# Servo_tester_Shematic.net
KiCad netlist of a schematic drawn in EasyEDA Pro
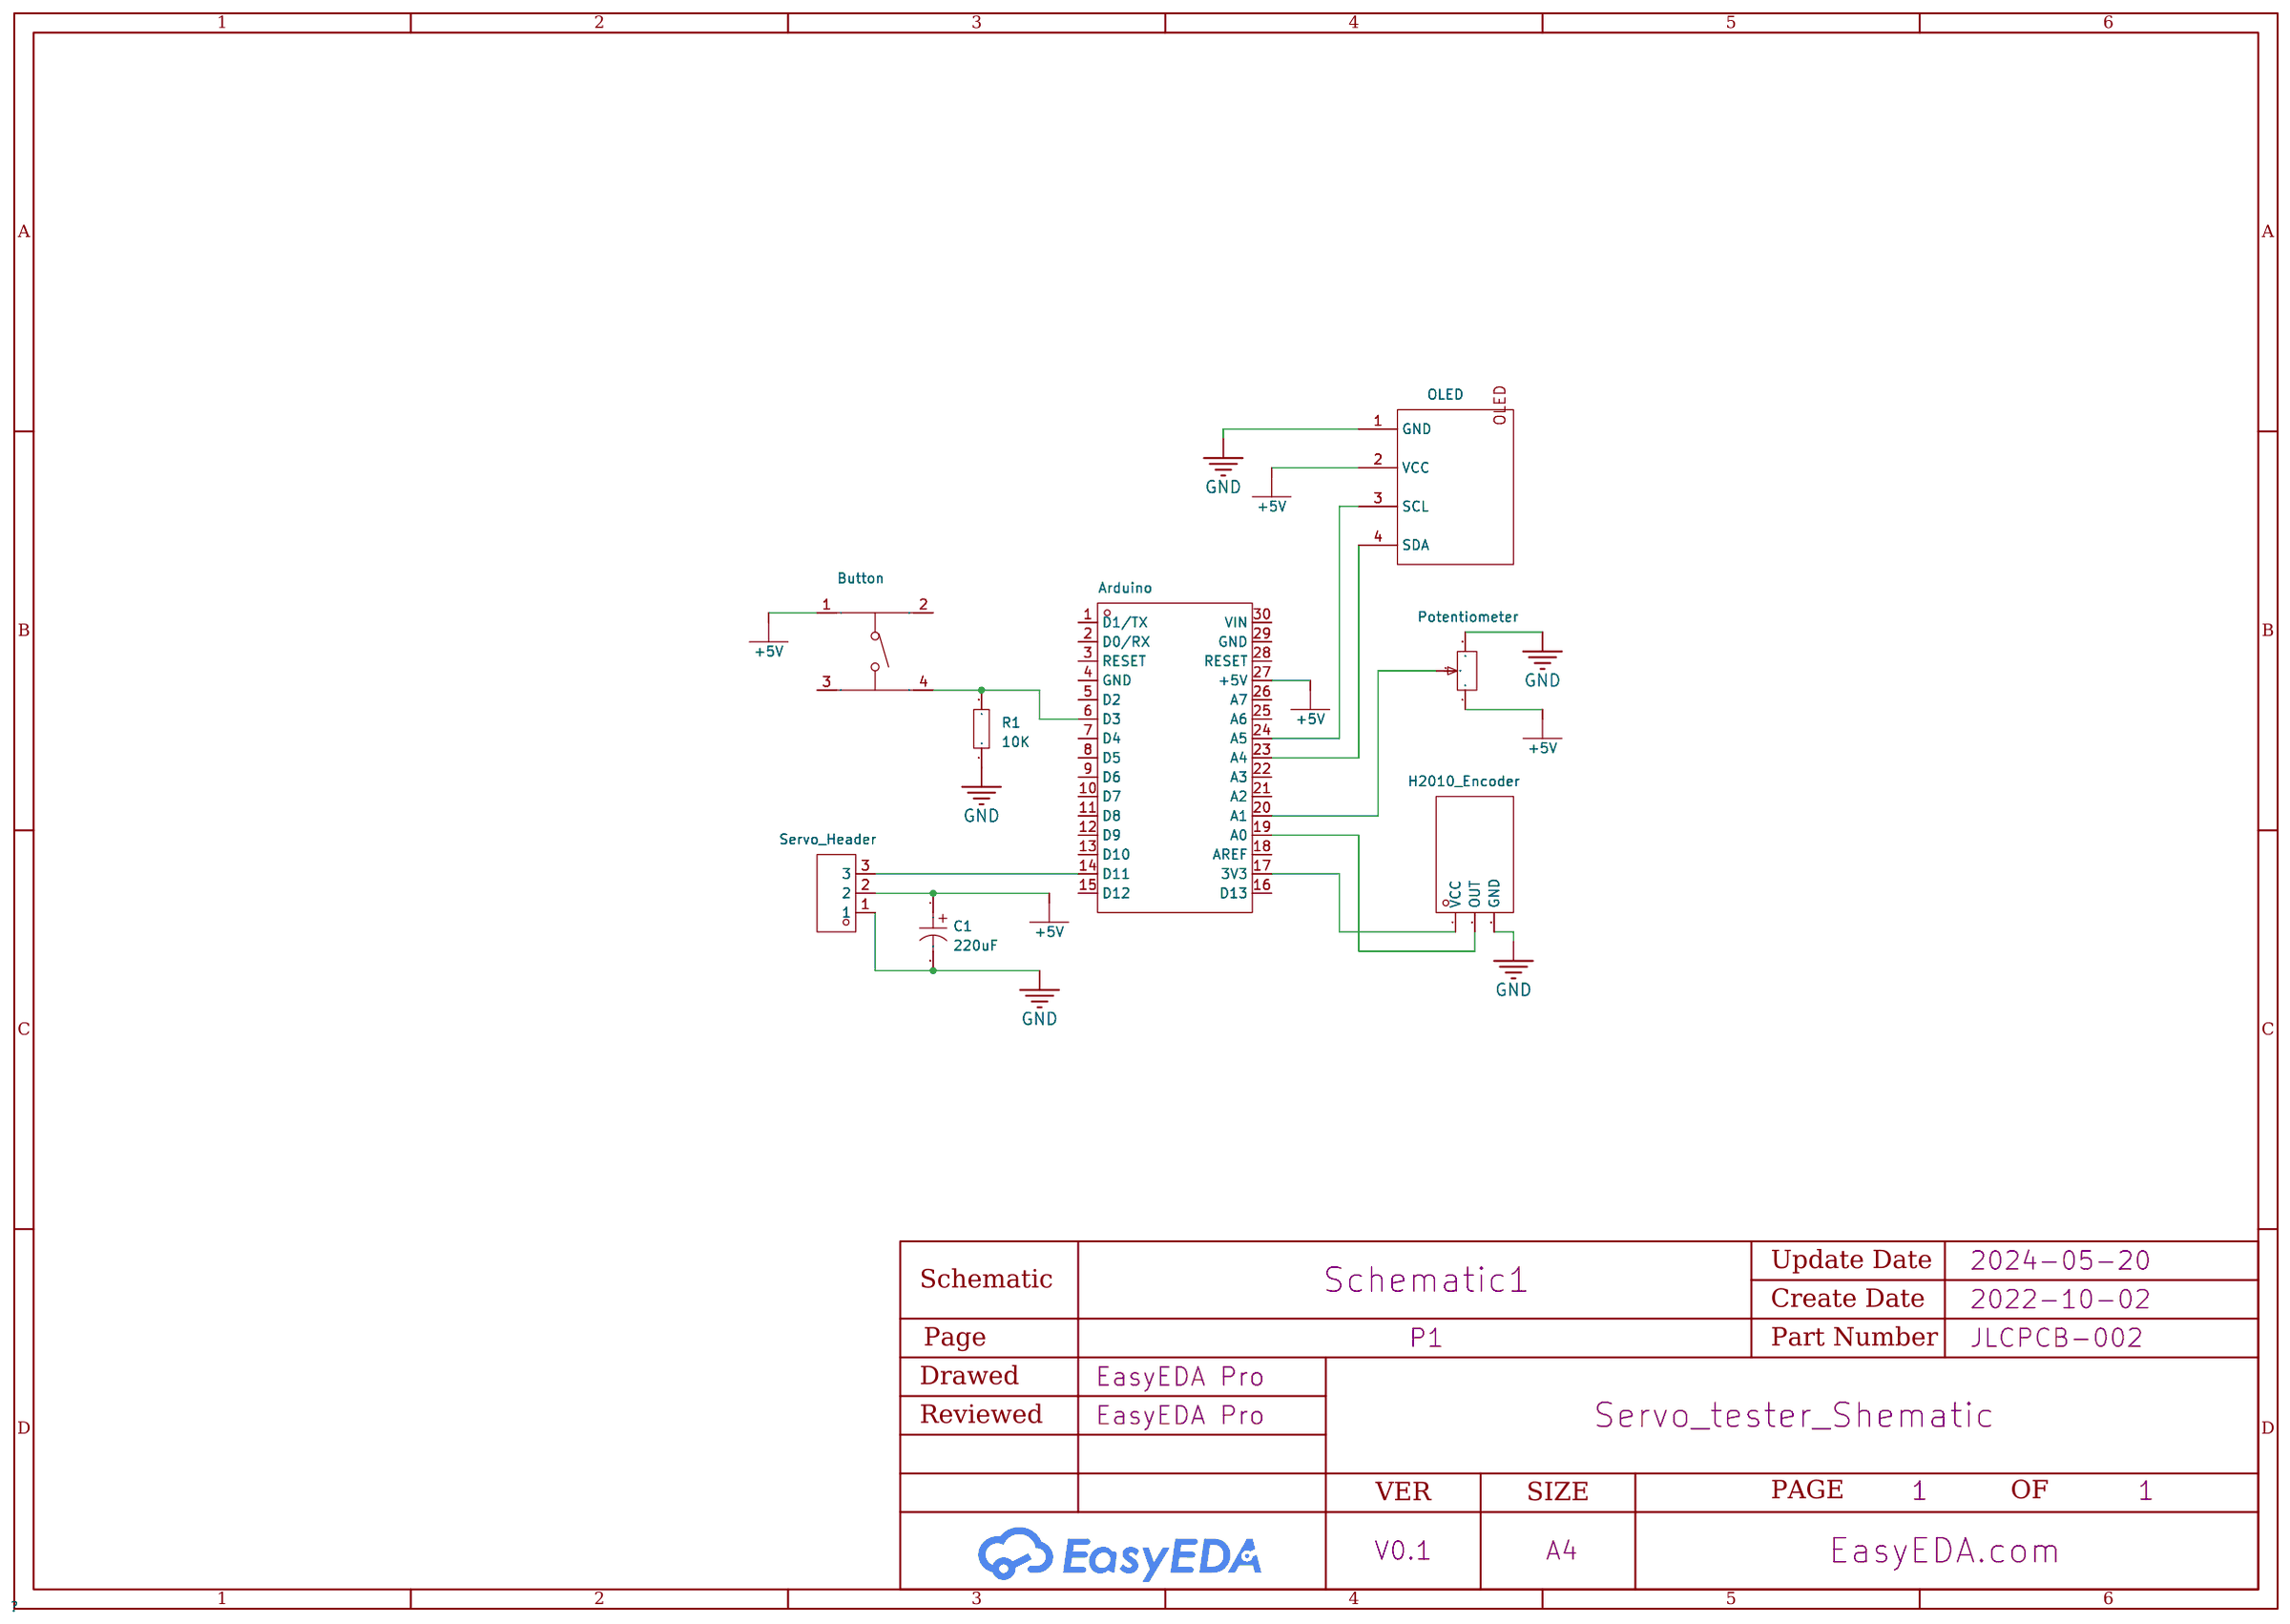
[diagram p0: schematic sheet]

(export (version "E")
  (design (tool "Eeschema 10.0.6"))
  (components
    (comp (ref "Arduino")
      (value "~")
      (footprint "easyedapro:COMM-TH_ARDUINO_NANO")
      (fields (field (name "Manufacturer Part") "ARDUINO_NANO"))
      (libsource (lib "easyedapro") (part "ARDUINO_NANO"))
    )
    (comp (ref "C1")
      (value "220uF")
      (footprint "easyedapro:CAP-TH_BD8.0-P3.50-D0.6-FD-2")
      (fields
        (field (name "Manufacturer Part") "KNH2220UF35V149EC0049")
        (field (name "Manufacturer") "KNSCHA(科尼盛)")
      )
      (libsource (lib "easyedapro") (part "KNH2220UF35V149EC0049"))
    )
    (comp (ref "H1")
      (value "Servo_Header")
      (footprint "easyedapro:HDR-TH_3P-P2.54-V-M")
      (fields
        (field (name "Manufacturer Part") "KH-2.54PH180-1X3P-L11.5")
        (field (name "Manufacturer") "kinghelm(金航标)")
      )
      (libsource (lib "easyedapro") (part "KH-2.54PH180-1X3P-L11.5"))
    )
    (comp (ref "H2010_Encoder")
      (value "POWER3-1")
      (footprint "easyedapro:CONN-TH_XH2.54-3P")
      (libsource (lib "easyedapro") (part "POWER3-1"))
    )
    (comp (ref "KEY1")
      (value "Button")
      (footprint "easyedapro:KEY-SMD_4P-L6.0-W6.0-P4.50-LS9.0")
      (libsource (lib "easyedapro") (part "BUTTON1"))
    )
    (comp (ref "OLED1")
      (value "OLED")
      (footprint "easyedapro:0.96OLED_4P")
      (fields (field (name "Manufacturer Part") "0.96OLED_4P_MODULE_JX"))
      (libsource (lib "easyedapro") (part "0.96OLED_4P_MODULE_JX"))
    )
    (comp (ref "R1")
      (value "10K")
      (footprint "easyedapro:RES-TH_BD2.5-L7.0-P11.00-D0.6-A")
      (libsource (lib "easyedapro") (part "10K_C9900023230"))
    )
    (comp (ref "U2")
      (value "Potentiometer")
      (footprint "easyedapro:RES-ADJ-SMD_VG039NCH")
      (fields (field (name "Manufacturer Part") "3*3Potentiometer-10kΩ20%"))
      (libsource (lib "easyedapro") (part "3*3POTENTIOMETER-10KΩ20%"))
    )
  )
  (nets
    (net (code "1") (name "+5V") (class "Default")
      (node (ref "Arduino") (pin "27") (pinfunction "+5V_27") (pintype "input"))
      (node (ref "C1") (pin "1") (pinfunction "1_1") (pintype "input"))
      (node (ref "H1") (pin "2") (pinfunction "2_2") (pintype "input"))
      (node (ref "KEY1") (pin "1") (pinfunction "1_1") (pintype "input"))
      (node (ref "OLED1") (pin "2") (pinfunction "VCC_2") (pintype "input"))
      (node (ref "U2") (pin "1") (pinfunction "1_1") (pintype "input"))
    )
    (net (code "2") (name "GND") (class "Default")
      (node (ref "C1") (pin "2") (pinfunction "2_2") (pintype "input"))
      (node (ref "H1") (pin "1") (pinfunction "1_1") (pintype "input"))
      (node (ref "H2010_Encoder") (pin "3") (pinfunction "GND_3") (pintype "unspecified"))
      (node (ref "OLED1") (pin "1") (pinfunction "GND_1") (pintype "input"))
      (node (ref "R1") (pin "1") (pinfunction "1_1") (pintype "input"))
      (node (ref "U2") (pin "3") (pinfunction "3_3") (pintype "input"))
    )
    (net (code "3") (name "Net-(Arduino-3V3)") (class "Default")
      (node (ref "Arduino") (pin "17") (pinfunction "3V3_17") (pintype "input"))
      (node (ref "H2010_Encoder") (pin "1") (pinfunction "VCC_1") (pintype "unspecified"))
    )
    (net (code "4") (name "Net-(Arduino-A0)") (class "Default")
      (node (ref "Arduino") (pin "19") (pinfunction "A0_19") (pintype "input"))
      (node (ref "H2010_Encoder") (pin "2") (pinfunction "OUT_2") (pintype "unspecified"))
    )
    (net (code "5") (name "Net-(Arduino-A1)") (class "Default")
      (node (ref "Arduino") (pin "20") (pinfunction "A1_20") (pintype "input"))
      (node (ref "U2") (pin "2") (pinfunction "2_2") (pintype "input"))
    )
    (net (code "6") (name "Net-(Arduino-A4)") (class "Default")
      (node (ref "Arduino") (pin "23") (pinfunction "A4_23") (pintype "input"))
      (node (ref "OLED1") (pin "4") (pinfunction "SDA_4") (pintype "input"))
    )
    (net (code "7") (name "Net-(Arduino-A5)") (class "Default")
      (node (ref "Arduino") (pin "24") (pinfunction "A5_24") (pintype "input"))
      (node (ref "OLED1") (pin "3") (pinfunction "SCL_3") (pintype "input"))
    )
    (net (code "8") (name "Net-(Arduino-D3)") (class "Default")
      (node (ref "Arduino") (pin "6") (pinfunction "D3_6") (pintype "input"))
      (node (ref "KEY1") (pin "4") (pinfunction "4_4") (pintype "input"))
      (node (ref "R1") (pin "2") (pinfunction "2_2") (pintype "input"))
    )
    (net (code "9") (name "Net-(Arduino-D11)") (class "Default")
      (node (ref "Arduino") (pin "14") (pinfunction "D11_14") (pintype "input"))
      (node (ref "H1") (pin "3") (pinfunction "3_3") (pintype "input"))
    )
    (net (code "10") (name "unconnected-(Arduino-A2-Pad21)") (class "Default")
      (node (ref "Arduino") (pin "21") (pinfunction "A2_21") (pintype "input"))
    )
    (net (code "11") (name "unconnected-(Arduino-A3-Pad22)") (class "Default")
      (node (ref "Arduino") (pin "22") (pinfunction "A3_22") (pintype "input"))
    )
    (net (code "12") (name "unconnected-(Arduino-A6-Pad25)") (class "Default")
      (node (ref "Arduino") (pin "25") (pinfunction "A6_25") (pintype "input"))
    )
    (net (code "13") (name "unconnected-(Arduino-A7-Pad26)") (class "Default")
      (node (ref "Arduino") (pin "26") (pinfunction "A7_26") (pintype "input"))
    )
    (net (code "14") (name "unconnected-(Arduino-AREF-Pad18)") (class "Default")
      (node (ref "Arduino") (pin "18") (pinfunction "AREF_18") (pintype "input"))
    )
    (net (code "15") (name "unconnected-(Arduino-D0{slash}RX-Pad2)") (class "Default")
      (node (ref "Arduino") (pin "2") (pinfunction "D0/RX_2") (pintype "input"))
    )
    (net (code "16") (name "unconnected-(Arduino-D1{slash}TX-Pad1)") (class "Default")
      (node (ref "Arduino") (pin "1") (pinfunction "D1/TX_1") (pintype "input"))
    )
    (net (code "17") (name "unconnected-(Arduino-D2-Pad5)") (class "Default")
      (node (ref "Arduino") (pin "5") (pinfunction "D2_5") (pintype "input"))
    )
    (net (code "18") (name "unconnected-(Arduino-D4-Pad7)") (class "Default")
      (node (ref "Arduino") (pin "7") (pinfunction "D4_7") (pintype "input"))
    )
    (net (code "19") (name "unconnected-(Arduino-D5-Pad8)") (class "Default")
      (node (ref "Arduino") (pin "8") (pinfunction "D5_8") (pintype "input"))
    )
    (net (code "20") (name "unconnected-(Arduino-D6-Pad9)") (class "Default")
      (node (ref "Arduino") (pin "9") (pinfunction "D6_9") (pintype "input"))
    )
    (net (code "21") (name "unconnected-(Arduino-D7-Pad10)") (class "Default")
      (node (ref "Arduino") (pin "10") (pinfunction "D7_10") (pintype "input"))
    )
    (net (code "22") (name "unconnected-(Arduino-D8-Pad11)") (class "Default")
      (node (ref "Arduino") (pin "11") (pinfunction "D8_11") (pintype "input"))
    )
    (net (code "23") (name "unconnected-(Arduino-D9-Pad12)") (class "Default")
      (node (ref "Arduino") (pin "12") (pinfunction "D9_12") (pintype "input"))
    )
    (net (code "24") (name "unconnected-(Arduino-D10-Pad13)") (class "Default")
      (node (ref "Arduino") (pin "13") (pinfunction "D10_13") (pintype "input"))
    )
    (net (code "25") (name "unconnected-(Arduino-D12-Pad15)") (class "Default")
      (node (ref "Arduino") (pin "15") (pinfunction "D12_15") (pintype "input"))
    )
    (net (code "26") (name "unconnected-(Arduino-D13-Pad16)") (class "Default")
      (node (ref "Arduino") (pin "16") (pinfunction "D13_16") (pintype "input"))
    )
    (net (code "27") (name "unconnected-(Arduino-GND-Pad4)") (class "Default")
      (node (ref "Arduino") (pin "4") (pinfunction "GND_4") (pintype "input"))
    )
    (net (code "28") (name "unconnected-(Arduino-GND-Pad29)") (class "Default")
      (node (ref "Arduino") (pin "29") (pinfunction "GND_29") (pintype "input"))
    )
    (net (code "29") (name "unconnected-(Arduino-RESET-Pad3)") (class "Default")
      (node (ref "Arduino") (pin "3") (pinfunction "RESET_3") (pintype "input"))
    )
    (net (code "30") (name "unconnected-(Arduino-RESET-Pad28)") (class "Default")
      (node (ref "Arduino") (pin "28") (pinfunction "RESET_28") (pintype "input"))
    )
    (net (code "31") (name "unconnected-(Arduino-VIN-Pad30)") (class "Default")
      (node (ref "Arduino") (pin "30") (pinfunction "VIN_30") (pintype "input"))
    )
    (net (code "32") (name "unconnected-(KEY1-Pad2)") (class "Default")
      (node (ref "KEY1") (pin "2") (pinfunction "2_2") (pintype "input"))
    )
    (net (code "33") (name "unconnected-(KEY1-Pad3)") (class "Default")
      (node (ref "KEY1") (pin "3") (pinfunction "3_3") (pintype "input"))
    )
  )
)
